# 8_step_seq_SMT.net
KiCad netlist of a schematic drawn in Altium Designer
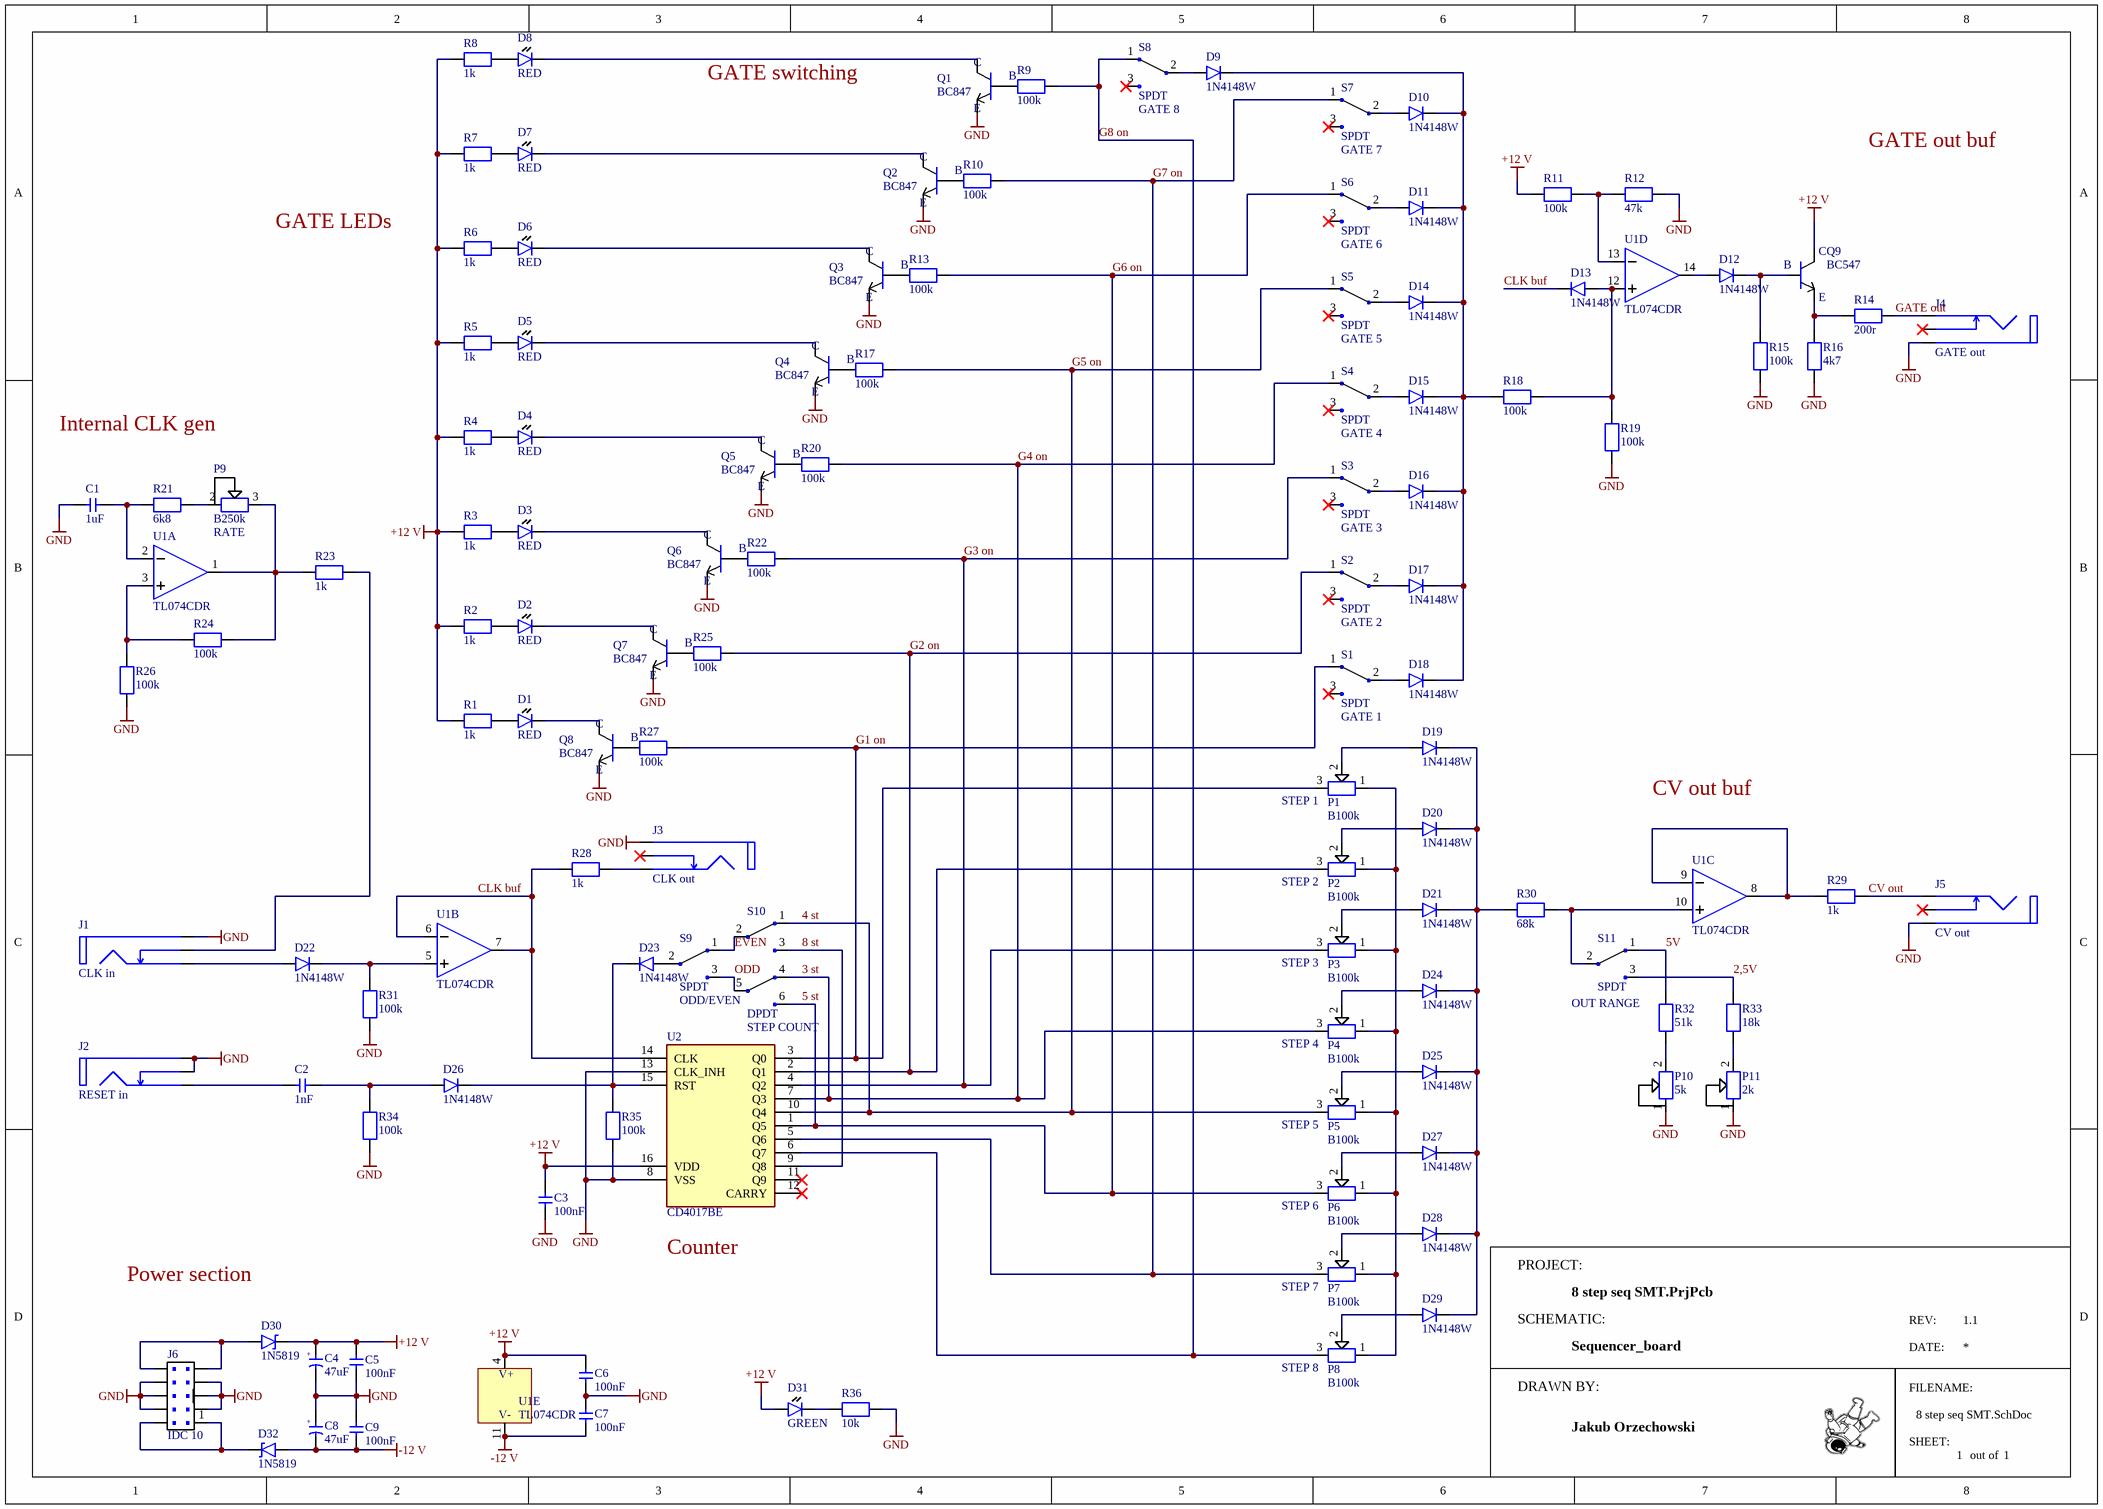
[diagram p0: 8 step seq SMT.SchDoc]

(export (version "E")
  (design (tool "Eeschema 10.0.6"))
  (components
    (comp (ref "C1")
      (value "1uF")
      (footprint "Cap SMD 0805")
      (description "SMD Capacitor Non-Polarised 0805 Package")
      (fields (field (name "Comment") "CAP"))
      (libsource (lib "Generic components") (part "Capacitor SMD 0805"))
    )
    (comp (ref "C2")
      (value "1nF")
      (footprint "Cap SMD 0805")
      (description "SMD Capacitor Non-Polarised 0805 Package")
      (fields (field (name "Comment") "CAP"))
      (libsource (lib "Generic components") (part "Capacitor SMD 0805"))
    )
    (comp (ref "C3")
      (value "100nF")
      (footprint "Cap SMD 0805")
      (description "SMD Capacitor Non-Polarised 0805 Package")
      (fields (field (name "Comment") "CAP"))
      (libsource (lib "Generic components") (part "Capacitor SMD 0805"))
    )
    (comp (ref "C4")
      (value "47uF")
      (footprint "Cap electrolytic THT 5mm")
      (description "THT Electrolytic Capacitor 5 mm Diameter")
      (fields (field (name "Comment") "CAP"))
      (libsource (lib "Generic components") (part "Capacitor Electr THT 5mm"))
    )
    (comp (ref "C5")
      (value "100nF")
      (footprint "Cap SMD 0805")
      (description "SMD Capacitor Non-Polarised 0805 Package")
      (fields (field (name "Comment") "CAP"))
      (libsource (lib "Generic components") (part "Capacitor SMD 0805"))
    )
    (comp (ref "C6")
      (value "100nF")
      (footprint "Cap SMD 0805")
      (description "SMD Capacitor Non-Polarised 0805 Package")
      (fields (field (name "Comment") "CAP"))
      (libsource (lib "Generic components") (part "Capacitor SMD 0805"))
    )
    (comp (ref "C7")
      (value "100nF")
      (footprint "Cap SMD 0805")
      (description "SMD Capacitor Non-Polarised 0805 Package")
      (fields (field (name "Comment") "CAP"))
      (libsource (lib "Generic components") (part "Capacitor SMD 0805"))
    )
    (comp (ref "C8")
      (value "47uF")
      (footprint "Cap electrolytic THT 5mm")
      (description "THT Electrolytic Capacitor 5 mm Diameter")
      (fields (field (name "Comment") "CAP"))
      (libsource (lib "Generic components") (part "Capacitor Electr THT 5mm"))
    )
    (comp (ref "C9")
      (value "100nF")
      (footprint "Cap SMD 0805")
      (description "SMD Capacitor Non-Polarised 0805 Package")
      (fields (field (name "Comment") "CAP"))
      (libsource (lib "Generic components") (part "Capacitor SMD 0805"))
    )
    (comp (ref "D1")
      (value "LED")
      (footprint "LED THT 3 mm raised")
      (description "THT LED Diode 3 mm Diameter")
      (fields (field (name "COLOR") "RED"))
      (libsource (lib "Opto") (part "LED THT 3mm"))
    )
    (comp (ref "D2")
      (value "LED")
      (footprint "LED THT 3 mm raised")
      (description "THT LED Diode 3 mm Diameter")
      (fields (field (name "COLOR") "RED"))
      (libsource (lib "Opto") (part "LED THT 3mm"))
    )
    (comp (ref "D3")
      (value "LED")
      (footprint "LED THT 3 mm raised")
      (description "THT LED Diode 3 mm Diameter")
      (fields (field (name "COLOR") "RED"))
      (libsource (lib "Opto") (part "LED THT 3mm"))
    )
    (comp (ref "D4")
      (value "LED")
      (footprint "LED THT 3 mm raised")
      (description "THT LED Diode 3 mm Diameter")
      (fields (field (name "COLOR") "RED"))
      (libsource (lib "Opto") (part "LED THT 3mm"))
    )
    (comp (ref "D5")
      (value "LED")
      (footprint "LED THT 3 mm raised")
      (description "THT LED Diode 3 mm Diameter")
      (fields (field (name "COLOR") "RED"))
      (libsource (lib "Opto") (part "LED THT 3mm"))
    )
    (comp (ref "D6")
      (value "LED")
      (footprint "LED THT 3 mm raised")
      (description "THT LED Diode 3 mm Diameter")
      (fields (field (name "COLOR") "RED"))
      (libsource (lib "Opto") (part "LED THT 3mm"))
    )
    (comp (ref "D7")
      (value "LED")
      (footprint "LED THT 3 mm raised")
      (description "THT LED Diode 3 mm Diameter")
      (fields (field (name "COLOR") "RED"))
      (libsource (lib "Opto") (part "LED THT 3mm"))
    )
    (comp (ref "D8")
      (value "LED")
      (footprint "LED THT 3 mm raised")
      (description "THT LED Diode 3 mm Diameter")
      (fields (field (name "COLOR") "RED"))
      (libsource (lib "Opto") (part "LED THT 3mm"))
    )
    (comp (ref "D9")
      (value "DIODE")
      (footprint "SOD-123")
      (description "1N4148W SMD Diode SOD123 Package")
      (fields (field (name "MODEL") "1N4148W"))
      (libsource (lib "Diodes") (part "1N4148W"))
    )
    (comp (ref "D10")
      (value "DIODE")
      (footprint "SOD-123")
      (description "1N4148W SMD Diode SOD123 Package")
      (fields (field (name "MODEL") "1N4148W"))
      (libsource (lib "Diodes") (part "1N4148W"))
    )
    (comp (ref "D11")
      (value "DIODE")
      (footprint "SOD-123")
      (description "1N4148W SMD Diode SOD123 Package")
      (fields (field (name "MODEL") "1N4148W"))
      (libsource (lib "Diodes") (part "1N4148W"))
    )
    (comp (ref "D12")
      (value "DIODE")
      (footprint "SOD-123")
      (description "1N4148W SMD Diode SOD123 Package")
      (fields (field (name "MODEL") "1N4148W"))
      (libsource (lib "Diodes") (part "1N4148W"))
    )
    (comp (ref "D13")
      (value "DIODE")
      (footprint "SOD-123")
      (description "1N4148W SMD Diode SOD123 Package")
      (fields (field (name "MODEL") "1N4148W"))
      (libsource (lib "Diodes") (part "1N4148W"))
    )
    (comp (ref "D14")
      (value "DIODE")
      (footprint "SOD-123")
      (description "1N4148W SMD Diode SOD123 Package")
      (fields (field (name "MODEL") "1N4148W"))
      (libsource (lib "Diodes") (part "1N4148W"))
    )
    (comp (ref "D15")
      (value "DIODE")
      (footprint "SOD-123")
      (description "1N4148W SMD Diode SOD123 Package")
      (fields (field (name "MODEL") "1N4148W"))
      (libsource (lib "Diodes") (part "1N4148W"))
    )
    (comp (ref "D16")
      (value "DIODE")
      (footprint "SOD-123")
      (description "1N4148W SMD Diode SOD123 Package")
      (fields (field (name "MODEL") "1N4148W"))
      (libsource (lib "Diodes") (part "1N4148W"))
    )
    (comp (ref "D17")
      (value "DIODE")
      (footprint "SOD-123")
      (description "1N4148W SMD Diode SOD123 Package")
      (fields (field (name "MODEL") "1N4148W"))
      (libsource (lib "Diodes") (part "1N4148W"))
    )
    (comp (ref "D18")
      (value "DIODE")
      (footprint "SOD-123")
      (description "1N4148W SMD Diode SOD123 Package")
      (fields (field (name "MODEL") "1N4148W"))
      (libsource (lib "Diodes") (part "1N4148W"))
    )
    (comp (ref "D19")
      (value "DIODE")
      (footprint "SOD-123")
      (description "1N4148W SMD Diode SOD123 Package")
      (fields (field (name "MODEL") "1N4148W"))
      (libsource (lib "Diodes") (part "1N4148W"))
    )
    (comp (ref "D20")
      (value "DIODE")
      (footprint "SOD-123")
      (description "1N4148W SMD Diode SOD123 Package")
      (fields (field (name "MODEL") "1N4148W"))
      (libsource (lib "Diodes") (part "1N4148W"))
    )
    (comp (ref "D21")
      (value "DIODE")
      (footprint "SOD-123")
      (description "1N4148W SMD Diode SOD123 Package")
      (fields (field (name "MODEL") "1N4148W"))
      (libsource (lib "Diodes") (part "1N4148W"))
    )
    (comp (ref "D22")
      (value "DIODE")
      (footprint "SOD-123")
      (description "1N4148W SMD Diode SOD123 Package")
      (fields (field (name "MODEL") "1N4148W"))
      (libsource (lib "Diodes") (part "1N4148W"))
    )
    (comp (ref "D23")
      (value "DIODE")
      (footprint "SOD-123")
      (description "1N4148W SMD Diode SOD123 Package")
      (fields (field (name "MODEL") "1N4148W"))
      (libsource (lib "Diodes") (part "1N4148W"))
    )
    (comp (ref "D24")
      (value "DIODE")
      (footprint "SOD-123")
      (description "1N4148W SMD Diode SOD123 Package")
      (fields (field (name "MODEL") "1N4148W"))
      (libsource (lib "Diodes") (part "1N4148W"))
    )
    (comp (ref "D25")
      (value "DIODE")
      (footprint "SOD-123")
      (description "1N4148W SMD Diode SOD123 Package")
      (fields (field (name "MODEL") "1N4148W"))
      (libsource (lib "Diodes") (part "1N4148W"))
    )
    (comp (ref "D26")
      (value "DIODE")
      (footprint "SOD-123")
      (description "1N4148W SMD Diode SOD123 Package")
      (fields (field (name "MODEL") "1N4148W"))
      (libsource (lib "Diodes") (part "1N4148W"))
    )
    (comp (ref "D27")
      (value "DIODE")
      (footprint "SOD-123")
      (description "1N4148W SMD Diode SOD123 Package")
      (fields (field (name "MODEL") "1N4148W"))
      (libsource (lib "Diodes") (part "1N4148W"))
    )
    (comp (ref "D28")
      (value "DIODE")
      (footprint "SOD-123")
      (description "1N4148W SMD Diode SOD123 Package")
      (fields (field (name "MODEL") "1N4148W"))
      (libsource (lib "Diodes") (part "1N4148W"))
    )
    (comp (ref "D29")
      (value "DIODE")
      (footprint "SOD-123")
      (description "1N4148W SMD Diode SOD123 Package")
      (fields (field (name "MODEL") "1N4148W"))
      (libsource (lib "Diodes") (part "1N4148W"))
    )
    (comp (ref "D30")
      (value "SCHOTTKY")
      (footprint "Diode THT 10 mm")
      (description "Generic THT Axial Schottky Diode 10 mm Pitch")
      (fields (field (name "MODEL") "1N5819"))
      (libsource (lib "Diodes") (part "Schottky Diode THT"))
    )
    (comp (ref "D31")
      (value "LED")
      (footprint "LED SMD 0805")
      (description "SMD LED Diode 0805 Package")
      (fields (field (name "COLOR") "GREEN"))
      (libsource (lib "Opto") (part "LED SMD"))
    )
    (comp (ref "D32")
      (value "SCHOTTKY")
      (footprint "Diode THT 10 mm")
      (description "Generic THT Axial Schottky Diode 10 mm Pitch")
      (fields (field (name "MODEL") "1N5819"))
      (libsource (lib "Diodes") (part "Schottky Diode THT"))
    )
    (comp (ref "J1")
      (value "JACK Mono")
      (footprint "PJ301M")
      (description "PJ301M Eurorack 3,5 mm Patch Socket PCB Mount")
      (fields (field (name "LABEL") "CLK in"))
      (libsource (lib "Connectors") (part "PJ301M"))
    )
    (comp (ref "J2")
      (value "JACK Mono")
      (footprint "PJ301M")
      (description "PJ301M Eurorack 3,5 mm Patch Socket PCB Mount")
      (fields (field (name "LABEL") "RESET in"))
      (libsource (lib "Connectors") (part "PJ301M"))
    )
    (comp (ref "J3")
      (value "JACK Mono")
      (footprint "PJ301M")
      (description "PJ301M Eurorack 3,5 mm Patch Socket PCB Mount")
      (fields (field (name "LABEL") "CLK out"))
      (libsource (lib "Connectors") (part "PJ301M"))
    )
    (comp (ref "J4")
      (value "JACK Mono")
      (footprint "PJ301M")
      (description "PJ301M Eurorack 3,5 mm Patch Socket PCB Mount")
      (fields (field (name "LABEL") "GATE out"))
      (libsource (lib "Connectors") (part "PJ301M"))
    )
    (comp (ref "J5")
      (value "JACK Mono")
      (footprint "PJ301M")
      (description "PJ301M Eurorack 3,5 mm Patch Socket PCB Mount")
      (fields (field (name "LABEL") "CV out"))
      (libsource (lib "Connectors") (part "PJ301M"))
    )
    (comp (ref "J6")
      (value "IDC 10")
      (footprint "IDC 10 PIN")
      (description "10 Pin IDC Connector")
      (libsource (lib "Connectors") (part "IDC 10 pin"))
    )
    (comp (ref "P1")
      (value "B100k")
      (footprint "9 mm PCB Potentiometer")
      (description "PCB Mount 9mm Mono Potentiometer THT")
      (fields (field (name "PARAMETER") "STEP 1") (field (name "Comment") "Mono Pot"))
      (libsource (lib "Potentiometers") (part "Potentiometer 9 mm"))
    )
    (comp (ref "P2")
      (value "B100k")
      (footprint "9 mm PCB Potentiometer")
      (description "PCB Mount 9mm Mono Potentiometer THT")
      (fields (field (name "PARAMETER") "STEP 2") (field (name "Comment") "Mono Pot"))
      (libsource (lib "Potentiometers") (part "Potentiometer 9 mm"))
    )
    (comp (ref "P3")
      (value "B100k")
      (footprint "9 mm PCB Potentiometer")
      (description "PCB Mount 9mm Mono Potentiometer THT")
      (fields (field (name "PARAMETER") "STEP 3") (field (name "Comment") "Mono Pot"))
      (libsource (lib "Potentiometers") (part "Potentiometer 9 mm"))
    )
    (comp (ref "P4")
      (value "B100k")
      (footprint "9 mm PCB Potentiometer")
      (description "PCB Mount 9mm Mono Potentiometer THT")
      (fields (field (name "PARAMETER") "STEP 4") (field (name "Comment") "Mono Pot"))
      (libsource (lib "Potentiometers") (part "Potentiometer 9 mm"))
    )
    (comp (ref "P5")
      (value "B100k")
      (footprint "9 mm PCB Potentiometer")
      (description "PCB Mount 9mm Mono Potentiometer THT")
      (fields (field (name "PARAMETER") "STEP 5") (field (name "Comment") "Mono Pot"))
      (libsource (lib "Potentiometers") (part "Potentiometer 9 mm"))
    )
    (comp (ref "P6")
      (value "B100k")
      (footprint "9 mm PCB Potentiometer")
      (description "PCB Mount 9mm Mono Potentiometer THT")
      (fields (field (name "PARAMETER") "STEP 6") (field (name "Comment") "Mono Pot"))
      (libsource (lib "Potentiometers") (part "Potentiometer 9 mm"))
    )
    (comp (ref "P7")
      (value "B100k")
      (footprint "9 mm PCB Potentiometer")
      (description "PCB Mount 9mm Mono Potentiometer THT")
      (fields (field (name "PARAMETER") "STEP 7") (field (name "Comment") "Mono Pot"))
      (libsource (lib "Potentiometers") (part "Potentiometer 9 mm"))
    )
    (comp (ref "P8")
      (value "B100k")
      (footprint "9 mm PCB Potentiometer")
      (description "PCB Mount 9mm Mono Potentiometer THT")
      (fields (field (name "PARAMETER") "STEP 8") (field (name "Comment") "Mono Pot"))
      (libsource (lib "Potentiometers") (part "Potentiometer 9 mm"))
    )
    (comp (ref "P9")
      (value "B250k")
      (footprint "9 mm PCB Potentiometer")
      (description "PCB Mount 9mm Mono Potentiometer THT as Variable Resistor Clockwise Decrease")
      (fields (field (name "PARAMETER") "RATE") (field (name "Comment") "VR"))
      (libsource (lib "Potentiometers") (part "VR B 9 mm"))
    )
    (comp (ref "P10")
      (value "5k")
      (footprint "Multiturn Potentiometer inline")
      (description "PCB Mount Multiturn Trimmer Potentiometer Top Adjustable as Variable Resistor Clockwise Increase")
      (fields (field (name "Comment") "VR"))
      (libsource (lib "Potentiometers") (part "VR A Multiturn THT"))
    )
    (comp (ref "P11")
      (value "2k")
      (footprint "Multiturn Potentiometer inline")
      (description "PCB Mount Multiturn Trimmer Potentiometer Top Adjustable as Variable Resistor Clockwise Increase")
      (fields (field (name "Comment") "VR"))
      (libsource (lib "Potentiometers") (part "VR A Multiturn THT"))
    )
    (comp (ref "Q1")
      (value "BC847")
      (footprint "SOT-23-3")
      (description "BC847 NPN Transistor SMD SOT-23-3 Package")
      (libsource (lib "Transistors") (part "BC847"))
    )
    (comp (ref "Q2")
      (value "BC847")
      (footprint "SOT-23-3")
      (description "BC847 NPN Transistor SMD SOT-23-3 Package")
      (libsource (lib "Transistors") (part "BC847"))
    )
    (comp (ref "Q3")
      (value "BC847")
      (footprint "SOT-23-3")
      (description "BC847 NPN Transistor SMD SOT-23-3 Package")
      (libsource (lib "Transistors") (part "BC847"))
    )
    (comp (ref "Q4")
      (value "BC847")
      (footprint "SOT-23-3")
      (description "BC847 NPN Transistor SMD SOT-23-3 Package")
      (libsource (lib "Transistors") (part "BC847"))
    )
    (comp (ref "Q5")
      (value "BC847")
      (footprint "SOT-23-3")
      (description "BC847 NPN Transistor SMD SOT-23-3 Package")
      (libsource (lib "Transistors") (part "BC847"))
    )
    (comp (ref "Q6")
      (value "BC847")
      (footprint "SOT-23-3")
      (description "BC847 NPN Transistor SMD SOT-23-3 Package")
      (libsource (lib "Transistors") (part "BC847"))
    )
    (comp (ref "Q7")
      (value "BC847")
      (footprint "SOT-23-3")
      (description "BC847 NPN Transistor SMD SOT-23-3 Package")
      (libsource (lib "Transistors") (part "BC847"))
    )
    (comp (ref "Q8")
      (value "BC847")
      (footprint "SOT-23-3")
      (description "BC847 NPN Transistor SMD SOT-23-3 Package")
      (libsource (lib "Transistors") (part "BC847"))
    )
    (comp (ref "Q9")
      (value "BC547")
      (footprint "TO-92 wide")
      (description "BC547 NPN Transistor THT TO-92 Package")
      (libsource (lib "Transistors") (part "BC547"))
    )
    (comp (ref "R1")
      (value "1k")
      (footprint "Resistor SMD 0805")
      (description "SMD Resistor 0805 package")
      (fields (field (name "Comment") "RES"))
      (libsource (lib "Generic components") (part "Resistor SMD 0805"))
    )
    (comp (ref "R2")
      (value "1k")
      (footprint "Resistor SMD 0805")
      (description "SMD Resistor 0805 package")
      (fields (field (name "Comment") "RES"))
      (libsource (lib "Generic components") (part "Resistor SMD 0805"))
    )
    (comp (ref "R3")
      (value "1k")
      (footprint "Resistor SMD 0805")
      (description "SMD Resistor 0805 package")
      (fields (field (name "Comment") "RES"))
      (libsource (lib "Generic components") (part "Resistor SMD 0805"))
    )
    (comp (ref "R4")
      (value "1k")
      (footprint "Resistor SMD 0805")
      (description "SMD Resistor 0805 package")
      (fields (field (name "Comment") "RES"))
      (libsource (lib "Generic components") (part "Resistor SMD 0805"))
    )
    (comp (ref "R5")
      (value "1k")
      (footprint "Resistor SMD 0805")
      (description "SMD Resistor 0805 package")
      (fields (field (name "Comment") "RES"))
      (libsource (lib "Generic components") (part "Resistor SMD 0805"))
    )
    (comp (ref "R6")
      (value "1k")
      (footprint "Resistor SMD 0805")
      (description "SMD Resistor 0805 package")
      (fields (field (name "Comment") "RES"))
      (libsource (lib "Generic components") (part "Resistor SMD 0805"))
    )
    (comp (ref "R7")
      (value "1k")
      (footprint "Resistor SMD 0805")
      (description "SMD Resistor 0805 package")
      (fields (field (name "Comment") "RES"))
      (libsource (lib "Generic components") (part "Resistor SMD 0805"))
    )
    (comp (ref "R8")
      (value "1k")
      (footprint "Resistor SMD 0805")
      (description "SMD Resistor 0805 package")
      (fields (field (name "Comment") "RES"))
      (libsource (lib "Generic components") (part "Resistor SMD 0805"))
    )
    (comp (ref "R9")
      (value "100k")
      (footprint "Resistor SMD 0805")
      (description "SMD Resistor 0805 package")
      (fields (field (name "Comment") "RES"))
      (libsource (lib "Generic components") (part "Resistor SMD 0805"))
    )
    (comp (ref "R10")
      (value "100k")
      (footprint "Resistor SMD 0805")
      (description "SMD Resistor 0805 package")
      (fields (field (name "Comment") "RES"))
      (libsource (lib "Generic components") (part "Resistor SMD 0805"))
    )
    (comp (ref "R11")
      (value "100k")
      (footprint "Resistor SMD 0805")
      (description "SMD Resistor 0805 package")
      (fields (field (name "Comment") "RES"))
      (libsource (lib "Generic components") (part "Resistor SMD 0805"))
    )
    (comp (ref "R12")
      (value "47k")
      (footprint "Resistor SMD 0805")
      (description "SMD Resistor 0805 package")
      (fields (field (name "Comment") "RES"))
      (libsource (lib "Generic components") (part "Resistor SMD 0805"))
    )
    (comp (ref "R13")
      (value "100k")
      (footprint "Resistor SMD 0805")
      (description "SMD Resistor 0805 package")
      (fields (field (name "Comment") "RES"))
      (libsource (lib "Generic components") (part "Resistor SMD 0805"))
    )
    (comp (ref "R14")
      (value "200r")
      (footprint "Resistor SMD 0805")
      (description "SMD Resistor 0805 package")
      (fields (field (name "Comment") "RES"))
      (libsource (lib "Generic components") (part "Resistor SMD 0805"))
    )
    (comp (ref "R15")
      (value "100k")
      (footprint "Resistor SMD 0805")
      (description "SMD Resistor 0805 package")
      (fields (field (name "Comment") "RES"))
      (libsource (lib "Generic components") (part "Resistor SMD 0805"))
    )
    (comp (ref "R16")
      (value "4k7")
      (footprint "Resistor SMD 0805")
      (description "SMD Resistor 0805 package")
      (fields (field (name "Comment") "RES"))
      (libsource (lib "Generic components") (part "Resistor SMD 0805"))
    )
    (comp (ref "R17")
      (value "100k")
      (footprint "Resistor SMD 0805")
      (description "SMD Resistor 0805 package")
      (fields (field (name "Comment") "RES"))
      (libsource (lib "Generic components") (part "Resistor SMD 0805"))
    )
    (comp (ref "R18")
      (value "100k")
      (footprint "Resistor SMD 0805")
      (description "SMD Resistor 0805 package")
      (fields (field (name "Comment") "RES"))
      (libsource (lib "Generic components") (part "Resistor SMD 0805"))
    )
    (comp (ref "R19")
      (value "100k")
      (footprint "Resistor SMD 0805")
      (description "SMD Resistor 0805 package")
      (fields (field (name "Comment") "RES"))
      (libsource (lib "Generic components") (part "Resistor SMD 0805"))
    )
    (comp (ref "R20")
      (value "100k")
      (footprint "Resistor SMD 0805")
      (description "SMD Resistor 0805 package")
      (fields (field (name "Comment") "RES"))
      (libsource (lib "Generic components") (part "Resistor SMD 0805"))
    )
    (comp (ref "R21")
      (value "6k8")
      (footprint "Resistor THT 10mm")
      (description "THT Axial Resistor 10mm Pitch")
      (fields (field (name "Comment") "RES"))
      (libsource (lib "Generic components") (part "Resistor THT"))
    )
    (comp (ref "R22")
      (value "100k")
      (footprint "Resistor SMD 0805")
      (description "SMD Resistor 0805 package")
      (fields (field (name "Comment") "RES"))
      (libsource (lib "Generic components") (part "Resistor SMD 0805"))
    )
    (comp (ref "R23")
      (value "1k")
      (footprint "Resistor SMD 0805")
      (description "SMD Resistor 0805 package")
      (fields (field (name "Comment") "RES"))
      (libsource (lib "Generic components") (part "Resistor SMD 0805"))
    )
    (comp (ref "R24")
      (value "100k")
      (footprint "Resistor SMD 0805")
      (description "SMD Resistor 0805 package")
      (fields (field (name "Comment") "RES"))
      (libsource (lib "Generic components") (part "Resistor SMD 0805"))
    )
    (comp (ref "R25")
      (value "100k")
      (footprint "Resistor SMD 0805")
      (description "SMD Resistor 0805 package")
      (fields (field (name "Comment") "RES"))
      (libsource (lib "Generic components") (part "Resistor SMD 0805"))
    )
    (comp (ref "R26")
      (value "100k")
      (footprint "Resistor SMD 0805")
      (description "SMD Resistor 0805 package")
      (fields (field (name "Comment") "RES"))
      (libsource (lib "Generic components") (part "Resistor SMD 0805"))
    )
    (comp (ref "R27")
      (value "100k")
      (footprint "Resistor SMD 0805")
      (description "SMD Resistor 0805 package")
      (fields (field (name "Comment") "RES"))
      (libsource (lib "Generic components") (part "Resistor SMD 0805"))
    )
    (comp (ref "R28")
      (value "1k")
      (footprint "Resistor SMD 0805")
      (description "SMD Resistor 0805 package")
      (fields (field (name "Comment") "RES"))
      (libsource (lib "Generic components") (part "Resistor SMD 0805"))
    )
    (comp (ref "R29")
      (value "1k")
      (footprint "Resistor SMD 0805")
      (description "SMD Resistor 0805 package")
      (fields (field (name "Comment") "RES"))
      (libsource (lib "Generic components") (part "Resistor SMD 0805"))
    )
    (comp (ref "R30")
      (value "68k")
      (footprint "Resistor SMD 0805")
      (description "SMD Resistor 0805 package")
      (fields (field (name "Comment") "RES"))
      (libsource (lib "Generic components") (part "Resistor SMD 0805"))
    )
    (comp (ref "R31")
      (value "100k")
      (footprint "Resistor SMD 0805")
      (description "SMD Resistor 0805 package")
      (fields (field (name "Comment") "RES"))
      (libsource (lib "Generic components") (part "Resistor SMD 0805"))
    )
    (comp (ref "R32")
      (value "51k")
      (footprint "Resistor SMD 0805")
      (description "SMD Resistor 0805 package")
      (fields (field (name "Comment") "RES"))
      (libsource (lib "Generic components") (part "Resistor SMD 0805"))
    )
    (comp (ref "R33")
      (value "18k")
      (footprint "Resistor SMD 0805")
      (description "SMD Resistor 0805 package")
      (fields (field (name "Comment") "RES"))
      (libsource (lib "Generic components") (part "Resistor SMD 0805"))
    )
    (comp (ref "R34")
      (value "100k")
      (footprint "Resistor SMD 0805")
      (description "SMD Resistor 0805 package")
      (fields (field (name "Comment") "RES"))
      (libsource (lib "Generic components") (part "Resistor SMD 0805"))
    )
    (comp (ref "R35")
      (value "100k")
      (footprint "Resistor SMD 0805")
      (description "SMD Resistor 0805 package")
      (fields (field (name "Comment") "RES"))
      (libsource (lib "Generic components") (part "Resistor SMD 0805"))
    )
    (comp (ref "R36")
      (value "10k")
      (footprint "Resistor SMD 0805")
      (description "SMD Resistor 0805 package")
      (fields (field (name "Comment") "RES"))
      (libsource (lib "Generic components") (part "Resistor SMD 0805"))
    )
    (comp (ref "S1")
      (value "SPDT")
      (footprint "MTS-102")
      (description "Single Pole Double Throw on-on Switch")
      (fields (field (name "SIGNALS") "GATE 1"))
      (libsource (lib "Switches") (part "MTS-102"))
    )
    (comp (ref "S2")
      (value "SPDT")
      (footprint "MTS-102")
      (description "Single Pole Double Throw on-on Switch")
      (fields (field (name "SIGNALS") "GATE 2"))
      (libsource (lib "Switches") (part "MTS-102"))
    )
    (comp (ref "S3")
      (value "SPDT")
      (footprint "MTS-102")
      (description "Single Pole Double Throw on-on Switch")
      (fields (field (name "SIGNALS") "GATE 3"))
      (libsource (lib "Switches") (part "MTS-102"))
    )
    (comp (ref "S4")
      (value "SPDT")
      (footprint "MTS-102")
      (description "Single Pole Double Throw on-on Switch")
      (fields (field (name "SIGNALS") "GATE 4"))
      (libsource (lib "Switches") (part "MTS-102"))
    )
    (comp (ref "S5")
      (value "SPDT")
      (footprint "MTS-102")
      (description "Single Pole Double Throw on-on Switch")
      (fields (field (name "SIGNALS") "GATE 5"))
      (libsource (lib "Switches") (part "MTS-102"))
    )
    (comp (ref "S6")
      (value "SPDT")
      (footprint "MTS-102")
      (description "Single Pole Double Throw on-on Switch")
      (fields (field (name "SIGNALS") "GATE 6"))
      (libsource (lib "Switches") (part "MTS-102"))
    )
    (comp (ref "S7")
      (value "SPDT")
      (footprint "MTS-102")
      (description "Single Pole Double Throw on-on Switch")
      (fields (field (name "SIGNALS") "GATE 7"))
      (libsource (lib "Switches") (part "MTS-102"))
    )
    (comp (ref "S8")
      (value "SPDT")
      (footprint "MTS-102")
      (description "Single Pole Double Throw on-on Switch")
      (fields (field (name "SIGNALS") "GATE 8"))
      (libsource (lib "Switches") (part "MTS-102"))
    )
    (comp (ref "S9")
      (value "SPDT")
      (footprint "MTS-102")
      (description "Single Pole Double Throw on-on Switch")
      (fields (field (name "SIGNALS") "ODD/EVEN"))
      (libsource (lib "Switches") (part "MTS-102"))
    )
    (comp (ref "S10")
      (value "DPDT")
      (footprint "MTS-202")
      (description "Dual Pole Dual Throw on-on Switch")
      (fields (field (name "SIGNALS") "STEP COUNT"))
      (libsource (lib "Switches") (part "MTS-202"))
    )
    (comp (ref "S11")
      (value "SPDT")
      (footprint "MTS-102")
      (description "Single Pole Double Throw on-on Switch")
      (fields (field (name "SIGNALS") "OUT RANGE"))
      (libsource (lib "Switches") (part "MTS-102"))
    )
    (comp (ref "U1")
      (value "TL074CDR")
      (footprint "SOIC14")
      (description "TL074CDR Quad Op-Amp SOIC14 Package")
      (libsource (lib "OpAmps") (part "TL074CDR SOIC14"))
    )
    (comp (ref "U2")
      (value "CD4017BE")
      (footprint "DIP-16 socket")
      (description "CD4017BE CMOS Decade Counter DIP-16 Package")
      (libsource (lib "ICs") (part "CD4017BE DIP-16"))
    )
  )
  (nets
    (net (code "1") (name "+12 V") (class "Default")
      (node (ref "C3") (pin "2") (pintype "passive"))
      (node (ref "C4") (pin "2") (pintype "passive"))
      (node (ref "C5") (pin "2") (pintype "passive"))
      (node (ref "C6") (pin "2") (pintype "passive"))
      (node (ref "D30") (pin "2") (pintype "passive"))
      (node (ref "D31") (pin "1") (pintype "passive"))
      (node (ref "Q9") (pin "1") (pintype "passive"))
      (node (ref "R1") (pin "2") (pintype "passive"))
      (node (ref "R11") (pin "1") (pintype "passive"))
      (node (ref "R2") (pin "2") (pintype "passive"))
      (node (ref "R3") (pin "2") (pintype "passive"))
      (node (ref "R4") (pin "2") (pintype "passive"))
      (node (ref "R5") (pin "2") (pintype "passive"))
      (node (ref "R6") (pin "2") (pintype "passive"))
      (node (ref "R7") (pin "2") (pintype "passive"))
      (node (ref "R8") (pin "2") (pintype "passive"))
      (node (ref "U1") (pin "4") (pintype "passive"))
      (node (ref "U2") (pin "16") (pinfunction "VDD_16") (pintype "passive"))
    )
    (net (code "2") (name "-12 V") (class "Default")
      (node (ref "C7") (pin "1") (pintype "passive"))
      (node (ref "C8") (pin "1") (pintype "passive"))
      (node (ref "C9") (pin "1") (pintype "passive"))
      (node (ref "D32") (pin "1") (pintype "passive"))
      (node (ref "U1") (pin "11") (pintype "passive"))
    )
    (net (code "3") (name "/2,5V") (class "Default")
      (node (ref "R33") (pin "1") (pintype "passive"))
      (node (ref "S11") (pin "3") (pintype "passive"))
    )
    (net (code "4") (name "/3 st") (class "Default")
      (node (ref "P4") (pin "3") (pintype "passive"))
      (node (ref "R20") (pin "2") (pintype "passive"))
      (node (ref "S10") (pin "4") (pintype "passive"))
      (node (ref "S4") (pin "1") (pintype "passive"))
      (node (ref "U2") (pin "7") (pinfunction "Q3_7") (pintype "passive"))
    )
    (net (code "5") (name "/4 st") (class "Default")
      (node (ref "P5") (pin "3") (pintype "passive"))
      (node (ref "R17") (pin "2") (pintype "passive"))
      (node (ref "S10") (pin "1") (pintype "passive"))
      (node (ref "S5") (pin "1") (pintype "passive"))
      (node (ref "U2") (pin "10") (pinfunction "Q4_10") (pintype "passive"))
    )
    (net (code "6") (name "/5 st") (class "Default")
      (node (ref "P6") (pin "3") (pintype "passive"))
      (node (ref "R13") (pin "2") (pintype "passive"))
      (node (ref "S10") (pin "6") (pintype "passive"))
      (node (ref "S6") (pin "1") (pintype "passive"))
      (node (ref "U2") (pin "1") (pinfunction "Q5_1") (pintype "passive"))
    )
    (net (code "7") (name "/5V") (class "Default")
      (node (ref "R32") (pin "1") (pintype "passive"))
      (node (ref "S11") (pin "1") (pintype "passive"))
    )
    (net (code "8") (name "/8 st") (class "Default")
      (node (ref "S10") (pin "3") (pintype "passive"))
      (node (ref "U2") (pin "9") (pinfunction "Q8_9") (pintype "passive"))
    )
    (net (code "9") (name "/CLK buf") (class "Default")
      (node (ref "D13") (pin "2") (pintype "passive"))
      (node (ref "R28") (pin "2") (pintype "passive"))
      (node (ref "U1") (pin "6") (pintype "passive"))
      (node (ref "U1") (pin "7") (pintype "passive"))
      (node (ref "U2") (pin "14") (pinfunction "CLK_14") (pintype "passive"))
    )
    (net (code "10") (name "/CV out") (class "Default")
      (node (ref "J5") (pin "3") (pintype "passive"))
      (node (ref "R29") (pin "1") (pintype "passive"))
    )
    (net (code "11") (name "/EVEN") (class "Default")
      (node (ref "S10") (pin "2") (pintype "passive"))
      (node (ref "S9") (pin "1") (pintype "passive"))
    )
    (net (code "12") (name "/G1 on") (class "Default")
      (node (ref "P1") (pin "3") (pintype "passive"))
      (node (ref "R27") (pin "2") (pintype "passive"))
      (node (ref "S1") (pin "1") (pintype "passive"))
      (node (ref "U2") (pin "3") (pinfunction "Q0_3") (pintype "passive"))
    )
    (net (code "13") (name "/G2 on") (class "Default")
      (node (ref "P2") (pin "3") (pintype "passive"))
      (node (ref "R25") (pin "2") (pintype "passive"))
      (node (ref "S2") (pin "1") (pintype "passive"))
      (node (ref "U2") (pin "2") (pinfunction "Q1_2") (pintype "passive"))
    )
    (net (code "14") (name "/G3 on") (class "Default")
      (node (ref "P3") (pin "3") (pintype "passive"))
      (node (ref "R22") (pin "2") (pintype "passive"))
      (node (ref "S3") (pin "1") (pintype "passive"))
      (node (ref "U2") (pin "4") (pinfunction "Q2_4") (pintype "passive"))
    )
    (net (code "15") (name "/G7 on") (class "Default")
      (node (ref "P7") (pin "3") (pintype "passive"))
      (node (ref "R10") (pin "2") (pintype "passive"))
      (node (ref "S7") (pin "1") (pintype "passive"))
      (node (ref "U2") (pin "5") (pinfunction "Q6_5") (pintype "passive"))
    )
    (net (code "16") (name "/G8 on") (class "Default")
      (node (ref "P8") (pin "3") (pintype "passive"))
      (node (ref "R9") (pin "2") (pintype "passive"))
      (node (ref "S8") (pin "1") (pintype "passive"))
      (node (ref "U2") (pin "6") (pinfunction "Q7_6") (pintype "passive"))
    )
    (net (code "17") (name "/GATE out") (class "Default")
      (node (ref "J4") (pin "3") (pintype "passive"))
      (node (ref "R14") (pin "1") (pintype "passive"))
    )
    (net (code "18") (name "/ODD") (class "Default")
      (node (ref "S10") (pin "5") (pintype "passive"))
      (node (ref "S9") (pin "3") (pintype "passive"))
    )
    (net (code "19") (name "GND") (class "Default")
      (node (ref "C1") (pin "1") (pintype "passive"))
      (node (ref "C3") (pin "1") (pintype "passive"))
      (node (ref "C4") (pin "1") (pintype "passive"))
      (node (ref "C5") (pin "1") (pintype "passive"))
      (node (ref "C6") (pin "1") (pintype "passive"))
      (node (ref "C7") (pin "2") (pintype "passive"))
      (node (ref "C8") (pin "2") (pintype "passive"))
      (node (ref "C9") (pin "2") (pintype "passive"))
      (node (ref "J1") (pin "1") (pintype "passive"))
      (node (ref "J2") (pin "1") (pintype "passive"))
      (node (ref "J2") (pin "2") (pintype "passive"))
      (node (ref "J3") (pin "1") (pintype "passive"))
      (node (ref "J4") (pin "1") (pintype "passive"))
      (node (ref "J5") (pin "1") (pintype "passive"))
      (node (ref "J6") (pin "3") (pintype "passive"))
      (node (ref "J6") (pin "4") (pintype "passive"))
      (node (ref "J6") (pin "5") (pintype "passive"))
      (node (ref "J6") (pin "6") (pintype "passive"))
      (node (ref "J6") (pin "7") (pintype "passive"))
      (node (ref "J6") (pin "8") (pintype "passive"))
      (node (ref "P10") (pin "1") (pintype "passive"))
      (node (ref "P11") (pin "1") (pintype "passive"))
      (node (ref "Q1") (pin "2") (pintype "passive"))
      (node (ref "Q2") (pin "2") (pintype "passive"))
      (node (ref "Q3") (pin "2") (pintype "passive"))
      (node (ref "Q4") (pin "2") (pintype "passive"))
      (node (ref "Q5") (pin "2") (pintype "passive"))
      (node (ref "Q6") (pin "2") (pintype "passive"))
      (node (ref "Q7") (pin "2") (pintype "passive"))
      (node (ref "Q8") (pin "2") (pintype "passive"))
      (node (ref "R12") (pin "2") (pintype "passive"))
      (node (ref "R15") (pin "2") (pintype "passive"))
      (node (ref "R16") (pin "2") (pintype "passive"))
      (node (ref "R19") (pin "1") (pintype "passive"))
      (node (ref "R26") (pin "1") (pintype "passive"))
      (node (ref "R31") (pin "1") (pintype "passive"))
      (node (ref "R34") (pin "1") (pintype "passive"))
      (node (ref "R35") (pin "1") (pintype "passive"))
      (node (ref "R36") (pin "2") (pintype "passive"))
      (node (ref "U2") (pin "13") (pinfunction "CLK_INH_13") (pintype "passive"))
      (node (ref "U2") (pin "8") (pinfunction "VSS_8") (pintype "passive"))
    )
    (net (code "20") (name "Net-(C1-Pad2)") (class "Default")
      (node (ref "C1") (pin "2") (pintype "passive"))
      (node (ref "R21") (pin "1") (pintype "passive"))
      (node (ref "U1") (pin "2") (pintype "passive"))
    )
    (net (code "21") (name "Net-(C2-Pad1)") (class "Default")
      (node (ref "C2") (pin "1") (pintype "passive"))
      (node (ref "J2") (pin "3") (pintype "passive"))
    )
    (net (code "22") (name "Net-(C2-Pad2)") (class "Default")
      (node (ref "C2") (pin "2") (pintype "passive"))
      (node (ref "D26") (pin "1") (pintype "passive"))
      (node (ref "R34") (pin "2") (pintype "passive"))
    )
    (net (code "23") (name "Net-(D1-Pad1)") (class "Default")
      (node (ref "D1") (pin "1") (pintype "passive"))
      (node (ref "R1") (pin "1") (pintype "passive"))
    )
    (net (code "24") (name "Net-(D1-Pad2)") (class "Default")
      (node (ref "D1") (pin "2") (pintype "passive"))
      (node (ref "Q8") (pin "3") (pintype "passive"))
    )
    (net (code "25") (name "Net-(D2-Pad1)") (class "Default")
      (node (ref "D2") (pin "1") (pintype "passive"))
      (node (ref "R2") (pin "1") (pintype "passive"))
    )
    (net (code "26") (name "Net-(D2-Pad2)") (class "Default")
      (node (ref "D2") (pin "2") (pintype "passive"))
      (node (ref "Q7") (pin "3") (pintype "passive"))
    )
    (net (code "27") (name "Net-(D3-Pad1)") (class "Default")
      (node (ref "D3") (pin "1") (pintype "passive"))
      (node (ref "R3") (pin "1") (pintype "passive"))
    )
    (net (code "28") (name "Net-(D3-Pad2)") (class "Default")
      (node (ref "D3") (pin "2") (pintype "passive"))
      (node (ref "Q6") (pin "3") (pintype "passive"))
    )
    (net (code "29") (name "Net-(D4-Pad1)") (class "Default")
      (node (ref "D4") (pin "1") (pintype "passive"))
      (node (ref "R4") (pin "1") (pintype "passive"))
    )
    (net (code "30") (name "Net-(D4-Pad2)") (class "Default")
      (node (ref "D4") (pin "2") (pintype "passive"))
      (node (ref "Q5") (pin "3") (pintype "passive"))
    )
    (net (code "31") (name "Net-(D5-Pad1)") (class "Default")
      (node (ref "D5") (pin "1") (pintype "passive"))
      (node (ref "R5") (pin "1") (pintype "passive"))
    )
    (net (code "32") (name "Net-(D5-Pad2)") (class "Default")
      (node (ref "D5") (pin "2") (pintype "passive"))
      (node (ref "Q4") (pin "3") (pintype "passive"))
    )
    (net (code "33") (name "Net-(D6-Pad1)") (class "Default")
      (node (ref "D6") (pin "1") (pintype "passive"))
      (node (ref "R6") (pin "1") (pintype "passive"))
    )
    (net (code "34") (name "Net-(D6-Pad2)") (class "Default")
      (node (ref "D6") (pin "2") (pintype "passive"))
      (node (ref "Q3") (pin "3") (pintype "passive"))
    )
    (net (code "35") (name "Net-(D7-Pad1)") (class "Default")
      (node (ref "D7") (pin "1") (pintype "passive"))
      (node (ref "R7") (pin "1") (pintype "passive"))
    )
    (net (code "36") (name "Net-(D7-Pad2)") (class "Default")
      (node (ref "D7") (pin "2") (pintype "passive"))
      (node (ref "Q2") (pin "3") (pintype "passive"))
    )
    (net (code "37") (name "Net-(D8-Pad1)") (class "Default")
      (node (ref "D8") (pin "1") (pintype "passive"))
      (node (ref "R8") (pin "1") (pintype "passive"))
    )
    (net (code "38") (name "Net-(D8-Pad2)") (class "Default")
      (node (ref "D8") (pin "2") (pintype "passive"))
      (node (ref "Q1") (pin "3") (pintype "passive"))
    )
    (net (code "39") (name "Net-(D9-Pad1)") (class "Default")
      (node (ref "D9") (pin "1") (pintype "passive"))
      (node (ref "S8") (pin "2") (pintype "passive"))
    )
    (net (code "40") (name "Net-(D10-Pad1)") (class "Default")
      (node (ref "D10") (pin "1") (pintype "passive"))
      (node (ref "S7") (pin "2") (pintype "passive"))
    )
    (net (code "41") (name "Net-(D10-Pad2)") (class "Default")
      (node (ref "D10") (pin "2") (pintype "passive"))
      (node (ref "D11") (pin "2") (pintype "passive"))
      (node (ref "D14") (pin "2") (pintype "passive"))
      (node (ref "D15") (pin "2") (pintype "passive"))
      (node (ref "D16") (pin "2") (pintype "passive"))
      (node (ref "D17") (pin "2") (pintype "passive"))
      (node (ref "D18") (pin "2") (pintype "passive"))
      (node (ref "D9") (pin "2") (pintype "passive"))
      (node (ref "R18") (pin "1") (pintype "passive"))
    )
    (net (code "42") (name "Net-(D11-Pad1)") (class "Default")
      (node (ref "D11") (pin "1") (pintype "passive"))
      (node (ref "S6") (pin "2") (pintype "passive"))
    )
    (net (code "43") (name "Net-(D12-Pad1)") (class "Default")
      (node (ref "D12") (pin "1") (pintype "passive"))
      (node (ref "U1") (pin "14") (pintype "passive"))
    )
    (net (code "44") (name "Net-(D12-Pad2)") (class "Default")
      (node (ref "D12") (pin "2") (pintype "passive"))
      (node (ref "Q9") (pin "2") (pintype "passive"))
      (node (ref "R15") (pin "1") (pintype "passive"))
    )
    (net (code "45") (name "Net-(D13-Pad1)") (class "Default")
      (node (ref "D13") (pin "1") (pintype "passive"))
      (node (ref "R18") (pin "2") (pintype "passive"))
      (node (ref "R19") (pin "2") (pintype "passive"))
      (node (ref "U1") (pin "12") (pintype "passive"))
    )
    (net (code "46") (name "Net-(D14-Pad1)") (class "Default")
      (node (ref "D14") (pin "1") (pintype "passive"))
      (node (ref "S5") (pin "2") (pintype "passive"))
    )
    (net (code "47") (name "Net-(D15-Pad1)") (class "Default")
      (node (ref "D15") (pin "1") (pintype "passive"))
      (node (ref "S4") (pin "2") (pintype "passive"))
    )
    (net (code "48") (name "Net-(D16-Pad1)") (class "Default")
      (node (ref "D16") (pin "1") (pintype "passive"))
      (node (ref "S3") (pin "2") (pintype "passive"))
    )
    (net (code "49") (name "Net-(D17-Pad1)") (class "Default")
      (node (ref "D17") (pin "1") (pintype "passive"))
      (node (ref "S2") (pin "2") (pintype "passive"))
    )
    (net (code "50") (name "Net-(D18-Pad1)") (class "Default")
      (node (ref "D18") (pin "1") (pintype "passive"))
      (node (ref "S1") (pin "2") (pintype "passive"))
    )
    (net (code "51") (name "Net-(D19-Pad1)") (class "Default")
      (node (ref "D19") (pin "1") (pintype "passive"))
      (node (ref "P1") (pin "2") (pintype "passive"))
    )
    (net (code "52") (name "Net-(D19-Pad2)") (class "Default")
      (node (ref "D19") (pin "2") (pintype "passive"))
      (node (ref "D20") (pin "2") (pintype "passive"))
      (node (ref "D21") (pin "2") (pintype "passive"))
      (node (ref "D24") (pin "2") (pintype "passive"))
      (node (ref "D25") (pin "2") (pintype "passive"))
      (node (ref "D27") (pin "2") (pintype "passive"))
      (node (ref "D28") (pin "2") (pintype "passive"))
      (node (ref "D29") (pin "2") (pintype "passive"))
      (node (ref "R30") (pin "2") (pintype "passive"))
    )
    (net (code "53") (name "Net-(D20-Pad1)") (class "Default")
      (node (ref "D20") (pin "1") (pintype "passive"))
      (node (ref "P2") (pin "2") (pintype "passive"))
    )
    (net (code "54") (name "Net-(D21-Pad1)") (class "Default")
      (node (ref "D21") (pin "1") (pintype "passive"))
      (node (ref "P3") (pin "2") (pintype "passive"))
    )
    (net (code "55") (name "Net-(D22-Pad1)") (class "Default")
      (node (ref "D22") (pin "1") (pintype "passive"))
      (node (ref "J1") (pin "3") (pintype "passive"))
    )
    (net (code "56") (name "Net-(D22-Pad2)") (class "Default")
      (node (ref "D22") (pin "2") (pintype "passive"))
      (node (ref "R31") (pin "2") (pintype "passive"))
      (node (ref "U1") (pin "5") (pintype "passive"))
    )
    (net (code "57") (name "Net-(D23-Pad1)") (class "Default")
      (node (ref "D23") (pin "1") (pintype "passive"))
      (node (ref "S9") (pin "2") (pintype "passive"))
    )
    (net (code "58") (name "Net-(D24-Pad1)") (class "Default")
      (node (ref "D24") (pin "1") (pintype "passive"))
      (node (ref "P4") (pin "2") (pintype "passive"))
    )
    (net (code "59") (name "Net-(D25-Pad1)") (class "Default")
      (node (ref "D25") (pin "1") (pintype "passive"))
      (node (ref "P5") (pin "2") (pintype "passive"))
    )
    (net (code "60") (name "Net-(D27-Pad1)") (class "Default")
      (node (ref "D27") (pin "1") (pintype "passive"))
      (node (ref "P6") (pin "2") (pintype "passive"))
    )
    (net (code "61") (name "Net-(D28-Pad1)") (class "Default")
      (node (ref "D28") (pin "1") (pintype "passive"))
      (node (ref "P7") (pin "2") (pintype "passive"))
    )
    (net (code "62") (name "Net-(D29-Pad1)") (class "Default")
      (node (ref "D29") (pin "1") (pintype "passive"))
      (node (ref "P8") (pin "2") (pintype "passive"))
    )
    (net (code "63") (name "Net-(D30-Pad1)") (class "Default")
      (node (ref "D30") (pin "1") (pintype "passive"))
      (node (ref "J6") (pin "10") (pintype "passive"))
      (node (ref "J6") (pin "9") (pintype "passive"))
    )
    (net (code "64") (name "Net-(D31-Pad2)") (class "Default")
      (node (ref "D31") (pin "2") (pintype "passive"))
      (node (ref "R36") (pin "1") (pintype "passive"))
    )
    (net (code "65") (name "Net-(D32-Pad2)") (class "Default")
      (node (ref "D32") (pin "2") (pintype "passive"))
      (node (ref "J6") (pin "1") (pintype "passive"))
      (node (ref "J6") (pin "2") (pintype "passive"))
    )
    (net (code "66") (name "Net-(J1-Pad2)") (class "Default")
      (node (ref "J1") (pin "2") (pintype "passive"))
      (node (ref "R23") (pin "2") (pintype "passive"))
    )
    (net (code "67") (name "Net-(J3-Pad3)") (class "Default")
      (node (ref "J3") (pin "3") (pintype "passive"))
      (node (ref "R28") (pin "1") (pintype "passive"))
    )
    (net (code "68") (name "Net-(P1-Pad1)") (class "Default")
      (node (ref "P1") (pin "1") (pintype "passive"))
      (node (ref "P2") (pin "1") (pintype "passive"))
      (node (ref "P3") (pin "1") (pintype "passive"))
      (node (ref "P4") (pin "1") (pintype "passive"))
      (node (ref "P5") (pin "1") (pintype "passive"))
      (node (ref "P6") (pin "1") (pintype "passive"))
      (node (ref "P7") (pin "1") (pintype "passive"))
      (node (ref "P8") (pin "1") (pintype "passive"))
    )
    (net (code "69") (name "Net-(P9-Pad2)") (class "Default")
      (node (ref "P9") (pin "2") (pintype "passive"))
      (node (ref "R21") (pin "2") (pintype "passive"))
    )
    (net (code "70") (name "Net-(P9-Pad3)") (class "Default")
      (node (ref "P9") (pin "3") (pintype "passive"))
      (node (ref "R23") (pin "1") (pintype "passive"))
      (node (ref "R24") (pin "2") (pintype "passive"))
      (node (ref "U1") (pin "1") (pintype "passive"))
    )
    (net (code "71") (name "Net-(P10-Pad2)") (class "Default")
      (node (ref "P10") (pin "2") (pintype "passive"))
      (node (ref "R32") (pin "2") (pintype "passive"))
    )
    (net (code "72") (name "Net-(P11-Pad2)") (class "Default")
      (node (ref "P11") (pin "2") (pintype "passive"))
      (node (ref "R33") (pin "2") (pintype "passive"))
    )
    (net (code "73") (name "Net-(Q1-Pad1)") (class "Default")
      (node (ref "Q1") (pin "1") (pintype "passive"))
      (node (ref "R9") (pin "1") (pintype "passive"))
    )
    (net (code "74") (name "Net-(Q2-Pad1)") (class "Default")
      (node (ref "Q2") (pin "1") (pintype "passive"))
      (node (ref "R10") (pin "1") (pintype "passive"))
    )
    (net (code "75") (name "Net-(Q3-Pad1)") (class "Default")
      (node (ref "Q3") (pin "1") (pintype "passive"))
      (node (ref "R13") (pin "1") (pintype "passive"))
    )
    (net (code "76") (name "Net-(Q4-Pad1)") (class "Default")
      (node (ref "Q4") (pin "1") (pintype "passive"))
      (node (ref "R17") (pin "1") (pintype "passive"))
    )
    (net (code "77") (name "Net-(Q5-Pad1)") (class "Default")
      (node (ref "Q5") (pin "1") (pintype "passive"))
      (node (ref "R20") (pin "1") (pintype "passive"))
    )
    (net (code "78") (name "Net-(Q6-Pad1)") (class "Default")
      (node (ref "Q6") (pin "1") (pintype "passive"))
      (node (ref "R22") (pin "1") (pintype "passive"))
    )
    (net (code "79") (name "Net-(Q7-Pad1)") (class "Default")
      (node (ref "Q7") (pin "1") (pintype "passive"))
      (node (ref "R25") (pin "1") (pintype "passive"))
    )
    (net (code "80") (name "Net-(Q8-Pad1)") (class "Default")
      (node (ref "Q8") (pin "1") (pintype "passive"))
      (node (ref "R27") (pin "1") (pintype "passive"))
    )
    (net (code "81") (name "Net-(Q9-Pad3)") (class "Default")
      (node (ref "Q9") (pin "3") (pintype "passive"))
      (node (ref "R14") (pin "2") (pintype "passive"))
      (node (ref "R16") (pin "1") (pintype "passive"))
    )
    (net (code "82") (name "Net-(R11-Pad2)") (class "Default")
      (node (ref "R11") (pin "2") (pintype "passive"))
      (node (ref "R12") (pin "1") (pintype "passive"))
      (node (ref "U1") (pin "13") (pintype "passive"))
    )
    (net (code "83") (name "Net-(R24-Pad1)") (class "Default")
      (node (ref "R24") (pin "1") (pintype "passive"))
      (node (ref "R26") (pin "2") (pintype "passive"))
      (node (ref "U1") (pin "3") (pintype "passive"))
    )
    (net (code "84") (name "Net-(R29-Pad2)") (class "Default")
      (node (ref "R29") (pin "2") (pintype "passive"))
      (node (ref "U1") (pin "8") (pintype "passive"))
      (node (ref "U1") (pin "9") (pintype "passive"))
    )
    (net (code "85") (name "Net-(R30-Pad1)") (class "Default")
      (node (ref "R30") (pin "1") (pintype "passive"))
      (node (ref "S11") (pin "2") (pintype "passive"))
      (node (ref "U1") (pin "10") (pintype "passive"))
    )
    (net (code "86") (name "Net-(U2-RST)") (class "Default")
      (node (ref "D23") (pin "2") (pintype "passive"))
      (node (ref "D26") (pin "2") (pintype "passive"))
      (node (ref "R35") (pin "2") (pintype "passive"))
      (node (ref "U2") (pin "15") (pinfunction "RST_15") (pintype "passive"))
    )
    (net (code "87") (name "unconnected-(J3-Pad2)") (class "Default")
      (node (ref "J3") (pin "2") (pintype "passive+no_connect"))
    )
    (net (code "88") (name "unconnected-(J4-Pad2)") (class "Default")
      (node (ref "J4") (pin "2") (pintype "passive+no_connect"))
    )
    (net (code "89") (name "unconnected-(J5-Pad2)") (class "Default")
      (node (ref "J5") (pin "2") (pintype "passive+no_connect"))
    )
    (net (code "90") (name "unconnected-(S1-Pad3)") (class "Default")
      (node (ref "S1") (pin "3") (pintype "passive+no_connect"))
    )
    (net (code "91") (name "unconnected-(S2-Pad3)") (class "Default")
      (node (ref "S2") (pin "3") (pintype "passive+no_connect"))
    )
    (net (code "92") (name "unconnected-(S3-Pad3)") (class "Default")
      (node (ref "S3") (pin "3") (pintype "passive+no_connect"))
    )
    (net (code "93") (name "unconnected-(S4-Pad3)") (class "Default")
      (node (ref "S4") (pin "3") (pintype "passive+no_connect"))
    )
    (net (code "94") (name "unconnected-(S5-Pad3)") (class "Default")
      (node (ref "S5") (pin "3") (pintype "passive+no_connect"))
    )
    (net (code "95") (name "unconnected-(S6-Pad3)") (class "Default")
      (node (ref "S6") (pin "3") (pintype "passive+no_connect"))
    )
    (net (code "96") (name "unconnected-(S7-Pad3)") (class "Default")
      (node (ref "S7") (pin "3") (pintype "passive+no_connect"))
    )
    (net (code "97") (name "unconnected-(S8-Pad3)") (class "Default")
      (node (ref "S8") (pin "3") (pintype "passive+no_connect"))
    )
    (net (code "98") (name "unconnected-(U2-CARRY-Pad12)") (class "Default")
      (node (ref "U2") (pin "12") (pinfunction "CARRY_12") (pintype "passive+no_connect"))
    )
    (net (code "99") (name "unconnected-(U2-Q9-Pad11)") (class "Default")
      (node (ref "U2") (pin "11") (pinfunction "Q9_11") (pintype "passive+no_connect"))
    )
  )
)
